# analogheart_schem.net
KiCad netlist of a schematic drawn in Altium Designer
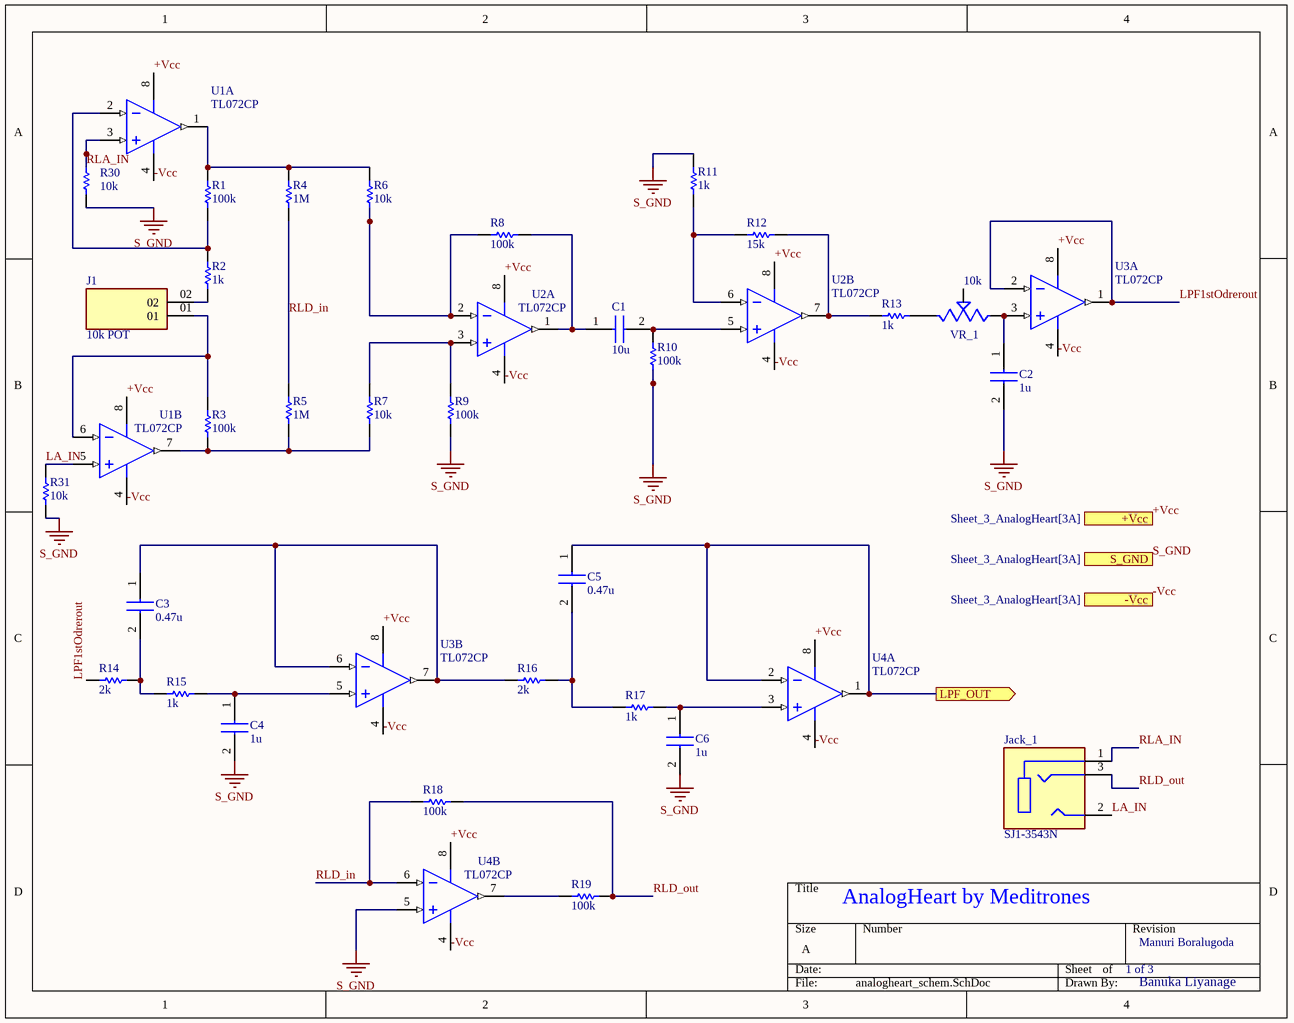
[diagram p0: analogheart_schem.SchDoc]

(export (version "E")
  (design (tool "Eeschema 10.0.6"))
  (components
    (comp (ref "C1")
      (value "10u")
      (footprint "SamacSys:CAPC2012X94N")
      (description "Capacitor")
      (fields
        (field (name "MANUFACTURER_PART_NUMBER") "08055A331FAT2A")
        (field (name "MOUSER PART NUMBER") "581-08055A331FAT2A")
      )
      (libsource (lib "*") (part "08055A331FAT2A"))
    )
    (comp (ref "C2")
      (value "1u")
      (footprint "SamacSys:CAPC2012X94N")
      (description "Capacitor")
      (fields
        (field (name "MANUFACTURER_PART_NUMBER") "08055A331FAT2A")
        (field (name "MOUSER PART NUMBER") "581-08055A331FAT2A")
      )
      (libsource (lib "*") (part "08055A331FAT2A"))
    )
    (comp (ref "C3")
      (value "0.47u")
      (footprint "SamacSys:CAPC2012X94N")
      (description "Capacitor")
      (fields
        (field (name "MANUFACTURER_PART_NUMBER") "08055A331FAT2A")
        (field (name "MOUSER PART NUMBER") "581-08055A331FAT2A")
      )
      (libsource (lib "*") (part "08055A331FAT2A"))
    )
    (comp (ref "C4")
      (value "1u")
      (footprint "SamacSys:CAPC2012X94N")
      (description "Capacitor")
      (fields
        (field (name "MANUFACTURER_PART_NUMBER") "08055A331FAT2A")
        (field (name "MOUSER PART NUMBER") "581-08055A331FAT2A")
      )
      (libsource (lib "*") (part "08055A331FAT2A"))
    )
    (comp (ref "C5")
      (value "0.47u")
      (footprint "SamacSys:CAPC2012X94N")
      (description "Capacitor")
      (fields
        (field (name "MANUFACTURER_PART_NUMBER") "08055A331FAT2A")
        (field (name "MOUSER PART NUMBER") "581-08055A331FAT2A")
      )
      (libsource (lib "*") (part "08055A331FAT2A"))
    )
    (comp (ref "C6")
      (value "1u")
      (footprint "SamacSys:CAPC2012X94N")
      (description "Capacitor")
      (fields
        (field (name "MANUFACTURER_PART_NUMBER") "08055A331FAT2A")
        (field (name "MOUSER PART NUMBER") "581-08055A331FAT2A")
      )
      (libsource (lib "*") (part "08055A331FAT2A"))
    )
    (comp (ref "J1")
      (value "10k POT")
      (footprint "SAMTEC_MTSW-102-11-T-S-640")
      (fields (field (name "MP") "MTSW-102-11-T-S-640"))
      (libsource (lib "MTSW-102-11-T-S-640") (part "MTSW-102-11-T-S-640"))
    )
    (comp (ref "Jack_1")
      (value "SJ1-3543N")
      (footprint "CUI_SJ1-3543N")
      (fields (field (name "MF") "{'manufacturer': u'CUI'}"))
      (libsource (lib "SJ1-3543N") (part "SJ1-3543N"))
    )
    (comp (ref "R1")
      (value "100k")
      (footprint "RESC2013X50X30NL20T20")
      (fields (field (name "MANUFACTURER") "Vishay Dale") (field (name "PART NUMBER") "CRCW080510R0FKEA"))
      (libsource (lib "Altium Content Vault") (part "RES"))
    )
    (comp (ref "R2")
      (value "1k")
      (footprint "RESC2013X50X30NL20T20")
      (fields (field (name "MANUFACTURER") "Vishay Dale") (field (name "PART NUMBER") "CRCW080510R0FKEA"))
      (libsource (lib "Altium Content Vault") (part "RES"))
    )
    (comp (ref "R3")
      (value "100k")
      (footprint "RESC2013X50X30NL20T20")
      (fields (field (name "MANUFACTURER") "Vishay Dale") (field (name "PART NUMBER") "CRCW080510R0FKEA"))
      (libsource (lib "Altium Content Vault") (part "RES"))
    )
    (comp (ref "R4")
      (value "1M")
      (footprint "RESC2013X50X30NL20T20")
      (fields (field (name "MANUFACTURER") "Vishay Dale") (field (name "PART NUMBER") "CRCW080510R0FKEA"))
      (libsource (lib "Altium Content Vault") (part "RES"))
    )
    (comp (ref "R5")
      (value "1M")
      (footprint "RESC2013X50X30NL20T20")
      (fields (field (name "MANUFACTURER") "Vishay Dale") (field (name "PART NUMBER") "CRCW080510R0FKEA"))
      (libsource (lib "Altium Content Vault") (part "RES"))
    )
    (comp (ref "R6")
      (value "10k")
      (footprint "RESC2013X50X30NL20T20")
      (fields (field (name "MANUFACTURER") "Vishay Dale") (field (name "PART NUMBER") "CRCW080510R0FKEA"))
      (libsource (lib "Altium Content Vault") (part "RES"))
    )
    (comp (ref "R7")
      (value "10k")
      (footprint "RESC2013X50X30NL20T20")
      (fields (field (name "MANUFACTURER") "Vishay Dale") (field (name "PART NUMBER") "CRCW080510R0FKEA"))
      (libsource (lib "Altium Content Vault") (part "RES"))
    )
    (comp (ref "R8")
      (value "100k")
      (footprint "RESC2013X50X30NL20T20")
      (fields (field (name "MANUFACTURER") "Vishay Dale") (field (name "PART NUMBER") "CRCW080510R0FKEA"))
      (libsource (lib "Altium Content Vault") (part "RES"))
    )
    (comp (ref "R9")
      (value "100k")
      (footprint "RESC2013X50X30NL20T20")
      (fields (field (name "MANUFACTURER") "Vishay Dale") (field (name "PART NUMBER") "CRCW080510R0FKEA"))
      (libsource (lib "Altium Content Vault") (part "RES"))
    )
    (comp (ref "R10")
      (value "100k")
      (footprint "RESC2013X50X30NL20T20")
      (fields (field (name "MANUFACTURER") "Vishay Dale") (field (name "PART NUMBER") "CRCW080510R0FKEA"))
      (libsource (lib "Altium Content Vault") (part "RES"))
    )
    (comp (ref "R11")
      (value "1k")
      (footprint "RESC2013X50X30NL20T20")
      (fields (field (name "MANUFACTURER") "Vishay Dale") (field (name "PART NUMBER") "CRCW080510R0FKEA"))
      (libsource (lib "Altium Content Vault") (part "RES"))
    )
    (comp (ref "R12")
      (value "15k")
      (footprint "RESC2013X50X30NL20T20")
      (fields (field (name "MANUFACTURER") "Vishay Dale") (field (name "PART NUMBER") "CRCW080510R0FKEA"))
      (libsource (lib "Altium Content Vault") (part "RES"))
    )
    (comp (ref "R13")
      (value "1k")
      (footprint "RESC2013X50X30NL20T20")
      (fields (field (name "MANUFACTURER") "Vishay Dale") (field (name "PART NUMBER") "CRCW080510R0FKEA"))
      (libsource (lib "Altium Content Vault") (part "RES"))
    )
    (comp (ref "R14")
      (value "2k")
      (footprint "RESC2013X50X30NL20T20")
      (fields (field (name "MANUFACTURER") "Vishay Dale") (field (name "PART NUMBER") "CRCW080510R0FKEA"))
      (libsource (lib "Altium Content Vault") (part "RES"))
    )
    (comp (ref "R15")
      (value "1k")
      (footprint "RESC2013X50X30NL20T20")
      (fields (field (name "MANUFACTURER") "Vishay Dale") (field (name "PART NUMBER") "CRCW080510R0FKEA"))
      (libsource (lib "Altium Content Vault") (part "RES"))
    )
    (comp (ref "R16")
      (value "2k")
      (footprint "RESC2013X50X30NL20T20")
      (fields (field (name "MANUFACTURER") "Vishay Dale") (field (name "PART NUMBER") "CRCW080510R0FKEA"))
      (libsource (lib "Altium Content Vault") (part "RES"))
    )
    (comp (ref "R17")
      (value "1k")
      (footprint "RESC2013X50X30NL20T20")
      (fields (field (name "MANUFACTURER") "Vishay Dale") (field (name "PART NUMBER") "CRCW080510R0FKEA"))
      (libsource (lib "Altium Content Vault") (part "RES"))
    )
    (comp (ref "R18")
      (value "100k")
      (footprint "RESC2013X50X30NL20T20")
      (fields (field (name "MANUFACTURER") "Vishay Dale") (field (name "PART NUMBER") "CRCW080510R0FKEA"))
      (libsource (lib "Altium Content Vault") (part "RES"))
    )
    (comp (ref "R19")
      (value "100k")
      (footprint "RESC2013X50X30NL20T20")
      (fields (field (name "MANUFACTURER") "Vishay Dale") (field (name "PART NUMBER") "CRCW080510R0FKEA"))
      (libsource (lib "Altium Content Vault") (part "RES"))
    )
    (comp (ref "R30")
      (value "10k")
      (footprint "RESC2013X50X30NL20T20")
      (fields (field (name "MANUFACTURER") "Vishay Dale") (field (name "PART NUMBER") "CRCW080510R0FKEA"))
      (libsource (lib "Altium Content Vault") (part "RES"))
    )
    (comp (ref "R31")
      (value "10k")
      (footprint "RESC2013X50X30NL20T20")
      (fields (field (name "MANUFACTURER") "Vishay Dale") (field (name "PART NUMBER") "CRCW080510R0FKEA"))
      (libsource (lib "Altium Content Vault") (part "RES"))
    )
    (comp (ref "U1")
      (value "TL072CP")
      (footprint "P0008A")
      (fields (field (name "MANUFACTURER") "Texas Instruments"))
      (libsource (lib "Altium Content Vault") (part "TI-AMP-D6-2-8_D"))
    )
    (comp (ref "U2")
      (value "TL072CP")
      (footprint "P0008A")
      (fields (field (name "MANUFACTURER") "Texas Instruments"))
      (libsource (lib "Altium Content Vault") (part "TI-AMP-D6-2-8_D"))
    )
    (comp (ref "U3")
      (value "TL072CP")
      (footprint "P0008A")
      (fields (field (name "MANUFACTURER") "Texas Instruments"))
      (libsource (lib "Altium Content Vault") (part "TI-AMP-D6-2-8_D"))
    )
    (comp (ref "U4")
      (value "TL072CP")
      (footprint "P0008A")
      (fields (field (name "MANUFACTURER") "Texas Instruments"))
      (libsource (lib "Altium Content Vault") (part "TI-AMP-D6-2-8_D"))
    )
    (comp (ref "VR_1")
      (value "10k")
      (footprint "TRIM_3386F-1-103TLF")
      (fields (field (name "MF") "Bourns") (field (name "MP") "3386F-1-103TLF"))
      (libsource (lib "3386F-1-103TLF") (part "3386F-1-103TLF"))
    )
  )
  (nets
    (net (code "1") (name "/+Vcc") (class "Default")
      (node (ref "U1") (pin "8") (pinfunction "VCC+_8") (pintype "power_in"))
      (node (ref "U2") (pin "8") (pinfunction "VCC+_8") (pintype "power_in"))
      (node (ref "U3") (pin "8") (pinfunction "VCC+_8") (pintype "power_in"))
      (node (ref "U4") (pin "8") (pinfunction "VCC+_8") (pintype "power_in"))
    )
    (net (code "2") (name "/-Vcc") (class "Default")
      (node (ref "U1") (pin "4") (pinfunction "VCC-_4") (pintype "power_in"))
      (node (ref "U2") (pin "4") (pinfunction "VCC-_4") (pintype "power_in"))
      (node (ref "U3") (pin "4") (pinfunction "VCC-_4") (pintype "power_in"))
      (node (ref "U4") (pin "4") (pinfunction "VCC-_4") (pintype "power_in"))
    )
    (net (code "3") (name "/LA_IN") (class "Default")
      (node (ref "Jack_1") (pin "2") (pinfunction "2_2") (pintype "passive"))
      (node (ref "R31") (pin "1") (pinfunction "1_1") (pintype "passive"))
      (node (ref "U1") (pin "5") (pinfunction "IN2+_5") (pintype "input"))
    )
    (net (code "4") (name "/LPF1stOdrerout") (class "Default")
      (node (ref "R14") (pin "2") (pinfunction "2_2") (pintype "passive"))
      (node (ref "U3") (pin "1") (pinfunction "OUT1_1") (pintype "output"))
      (node (ref "U3") (pin "2") (pinfunction "IN1-_2") (pintype "input"))
    )
    (net (code "5") (name "/LPF_OUT") (class "Default")
      (node (ref "C5") (pin "1") (pinfunction "1_1") (pintype "passive"))
      (node (ref "U4") (pin "1") (pinfunction "OUT1_1") (pintype "output"))
      (node (ref "U4") (pin "2") (pinfunction "IN1-_2") (pintype "input"))
    )
    (net (code "6") (name "/RLA_IN") (class "Default")
      (node (ref "Jack_1") (pin "1") (pinfunction "1_1") (pintype "passive"))
      (node (ref "R30") (pin "1") (pinfunction "1_1") (pintype "passive"))
      (node (ref "U1") (pin "3") (pinfunction "IN1+_3") (pintype "input"))
    )
    (net (code "7") (name "/RLD_in") (class "Default")
      (node (ref "R18") (pin "2") (pinfunction "2_2") (pintype "passive"))
      (node (ref "R4") (pin "1") (pinfunction "1_1") (pintype "passive"))
      (node (ref "R5") (pin "2") (pinfunction "2_2") (pintype "passive"))
      (node (ref "U4") (pin "6") (pinfunction "IN2-_6") (pintype "input"))
    )
    (net (code "8") (name "/RLD_out") (class "Default")
      (node (ref "Jack_1") (pin "3") (pinfunction "3_3") (pintype "passive"))
      (node (ref "R18") (pin "1") (pinfunction "1_1") (pintype "passive"))
      (node (ref "R19") (pin "1") (pinfunction "1_1") (pintype "passive"))
    )
    (net (code "9") (name "Net-(C3-Pad2)") (class "Default")
      (node (ref "C3") (pin "2") (pinfunction "2_2") (pintype "passive"))
      (node (ref "R14") (pin "1") (pinfunction "1_1") (pintype "passive"))
      (node (ref "R15") (pin "2") (pinfunction "2_2") (pintype "passive"))
    )
    (net (code "10") (name "Net-(C5-Pad2)") (class "Default")
      (node (ref "C5") (pin "2") (pinfunction "2_2") (pintype "passive"))
      (node (ref "R16") (pin "1") (pinfunction "1_1") (pintype "passive"))
      (node (ref "R17") (pin "2") (pinfunction "2_2") (pintype "passive"))
    )
    (net (code "11") (name "Net-(J1-Pad02)") (class "Default")
      (node (ref "J1") (pin "02") (pinfunction "02_02") (pintype "passive"))
      (node (ref "R2") (pin "1") (pinfunction "1_1") (pintype "passive"))
    )
    (net (code "12") (name "Net-(U1A-IN1-)") (class "Default")
      (node (ref "R1") (pin "1") (pinfunction "1_1") (pintype "passive"))
      (node (ref "R2") (pin "2") (pinfunction "2_2") (pintype "passive"))
      (node (ref "U1") (pin "2") (pinfunction "IN1-_2") (pintype "input"))
    )
    (net (code "13") (name "Net-(U1A-OUT1)") (class "Default")
      (node (ref "R1") (pin "2") (pinfunction "2_2") (pintype "passive"))
      (node (ref "R4") (pin "2") (pinfunction "2_2") (pintype "passive"))
      (node (ref "R6") (pin "2") (pinfunction "2_2") (pintype "passive"))
      (node (ref "U1") (pin "1") (pinfunction "OUT1_1") (pintype "output"))
    )
    (net (code "14") (name "Net-(U1B-IN2-)") (class "Default")
      (node (ref "J1") (pin "01") (pinfunction "01_01") (pintype "passive"))
      (node (ref "R3") (pin "2") (pinfunction "2_2") (pintype "passive"))
      (node (ref "U1") (pin "6") (pinfunction "IN2-_6") (pintype "input"))
    )
    (net (code "15") (name "Net-(U1B-OUT2)") (class "Default")
      (node (ref "R3") (pin "1") (pinfunction "1_1") (pintype "passive"))
      (node (ref "R5") (pin "1") (pinfunction "1_1") (pintype "passive"))
      (node (ref "R7") (pin "1") (pinfunction "1_1") (pintype "passive"))
      (node (ref "U1") (pin "7") (pinfunction "OUT2_7") (pintype "output"))
    )
    (net (code "16") (name "Net-(U2A-IN1+)") (class "Default")
      (node (ref "R7") (pin "2") (pinfunction "2_2") (pintype "passive"))
      (node (ref "R9") (pin "2") (pinfunction "2_2") (pintype "passive"))
      (node (ref "U2") (pin "3") (pinfunction "IN1+_3") (pintype "input"))
    )
    (net (code "17") (name "Net-(U2A-IN1-)") (class "Default")
      (node (ref "R6") (pin "1") (pinfunction "1_1") (pintype "passive"))
      (node (ref "R8") (pin "1") (pinfunction "1_1") (pintype "passive"))
      (node (ref "U2") (pin "2") (pinfunction "IN1-_2") (pintype "input"))
    )
    (net (code "18") (name "Net-(U2A-OUT1)") (class "Default")
      (node (ref "C1") (pin "1") (pinfunction "1_1") (pintype "passive"))
      (node (ref "R8") (pin "2") (pinfunction "2_2") (pintype "passive"))
      (node (ref "U2") (pin "1") (pinfunction "OUT1_1") (pintype "output"))
    )
    (net (code "19") (name "Net-(U2B-IN2+)") (class "Default")
      (node (ref "C1") (pin "2") (pinfunction "2_2") (pintype "passive"))
      (node (ref "R10") (pin "2") (pinfunction "2_2") (pintype "passive"))
      (node (ref "U2") (pin "5") (pinfunction "IN2+_5") (pintype "input"))
    )
    (net (code "20") (name "Net-(U2B-IN2-)") (class "Default")
      (node (ref "R11") (pin "1") (pinfunction "1_1") (pintype "passive"))
      (node (ref "R12") (pin "2") (pinfunction "2_2") (pintype "passive"))
      (node (ref "U2") (pin "6") (pinfunction "IN2-_6") (pintype "input"))
    )
    (net (code "21") (name "Net-(U2B-OUT2)") (class "Default")
      (node (ref "R12") (pin "1") (pinfunction "1_1") (pintype "passive"))
      (node (ref "R13") (pin "2") (pinfunction "2_2") (pintype "passive"))
      (node (ref "U2") (pin "7") (pinfunction "OUT2_7") (pintype "output"))
    )
    (net (code "22") (name "Net-(U3A-IN1+)") (class "Default")
      (node (ref "C2") (pin "1") (pinfunction "1_1") (pintype "passive"))
      (node (ref "U3") (pin "3") (pinfunction "IN1+_3") (pintype "input"))
      (node (ref "VR_1") (pin "1") (pinfunction "CCW_1") (pintype "passive"))
    )
    (net (code "23") (name "Net-(U3B-IN2+)") (class "Default")
      (node (ref "C4") (pin "1") (pinfunction "1_1") (pintype "passive"))
      (node (ref "R15") (pin "1") (pinfunction "1_1") (pintype "passive"))
      (node (ref "U3") (pin "5") (pinfunction "IN2+_5") (pintype "input"))
    )
    (net (code "24") (name "Net-(U3B-IN2-)") (class "Default")
      (node (ref "C3") (pin "1") (pinfunction "1_1") (pintype "passive"))
      (node (ref "R16") (pin "2") (pinfunction "2_2") (pintype "passive"))
      (node (ref "U3") (pin "6") (pinfunction "IN2-_6") (pintype "input"))
      (node (ref "U3") (pin "7") (pinfunction "OUT2_7") (pintype "output"))
    )
    (net (code "25") (name "Net-(U4A-IN1+)") (class "Default")
      (node (ref "C6") (pin "1") (pinfunction "1_1") (pintype "passive"))
      (node (ref "R17") (pin "1") (pinfunction "1_1") (pintype "passive"))
      (node (ref "U4") (pin "3") (pinfunction "IN1+_3") (pintype "input"))
    )
    (net (code "26") (name "Net-(U4B-OUT2)") (class "Default")
      (node (ref "R19") (pin "2") (pinfunction "2_2") (pintype "passive"))
      (node (ref "U4") (pin "7") (pinfunction "OUT2_7") (pintype "output"))
    )
    (net (code "27") (name "Net-(VR_1-CW)") (class "Default")
      (node (ref "R13") (pin "1") (pinfunction "1_1") (pintype "passive"))
      (node (ref "VR_1") (pin "3") (pinfunction "CW_3") (pintype "passive"))
    )
    (net (code "28") (name "S_GND") (class "Default")
      (node (ref "C2") (pin "2") (pinfunction "2_2") (pintype "passive"))
      (node (ref "C4") (pin "2") (pinfunction "2_2") (pintype "passive"))
      (node (ref "C6") (pin "2") (pinfunction "2_2") (pintype "passive"))
      (node (ref "R10") (pin "1") (pinfunction "1_1") (pintype "passive"))
      (node (ref "R11") (pin "2") (pinfunction "2_2") (pintype "passive"))
      (node (ref "R30") (pin "2") (pinfunction "2_2") (pintype "passive"))
      (node (ref "R31") (pin "2") (pinfunction "2_2") (pintype "passive"))
      (node (ref "R9") (pin "1") (pinfunction "1_1") (pintype "passive"))
      (node (ref "U4") (pin "5") (pinfunction "IN2+_5") (pintype "input"))
    )
    (net (code "29") (name "unconnected-(VR_1-WIPER-Pad2)") (class "Default")
      (node (ref "VR_1") (pin "2") (pinfunction "WIPER_2") (pintype "passive"))
    )
  )
)
